# ICS40300-Silicon-Mic_Rev-A_s_y.net
KiCad netlist of a schematic drawn in EAGLE
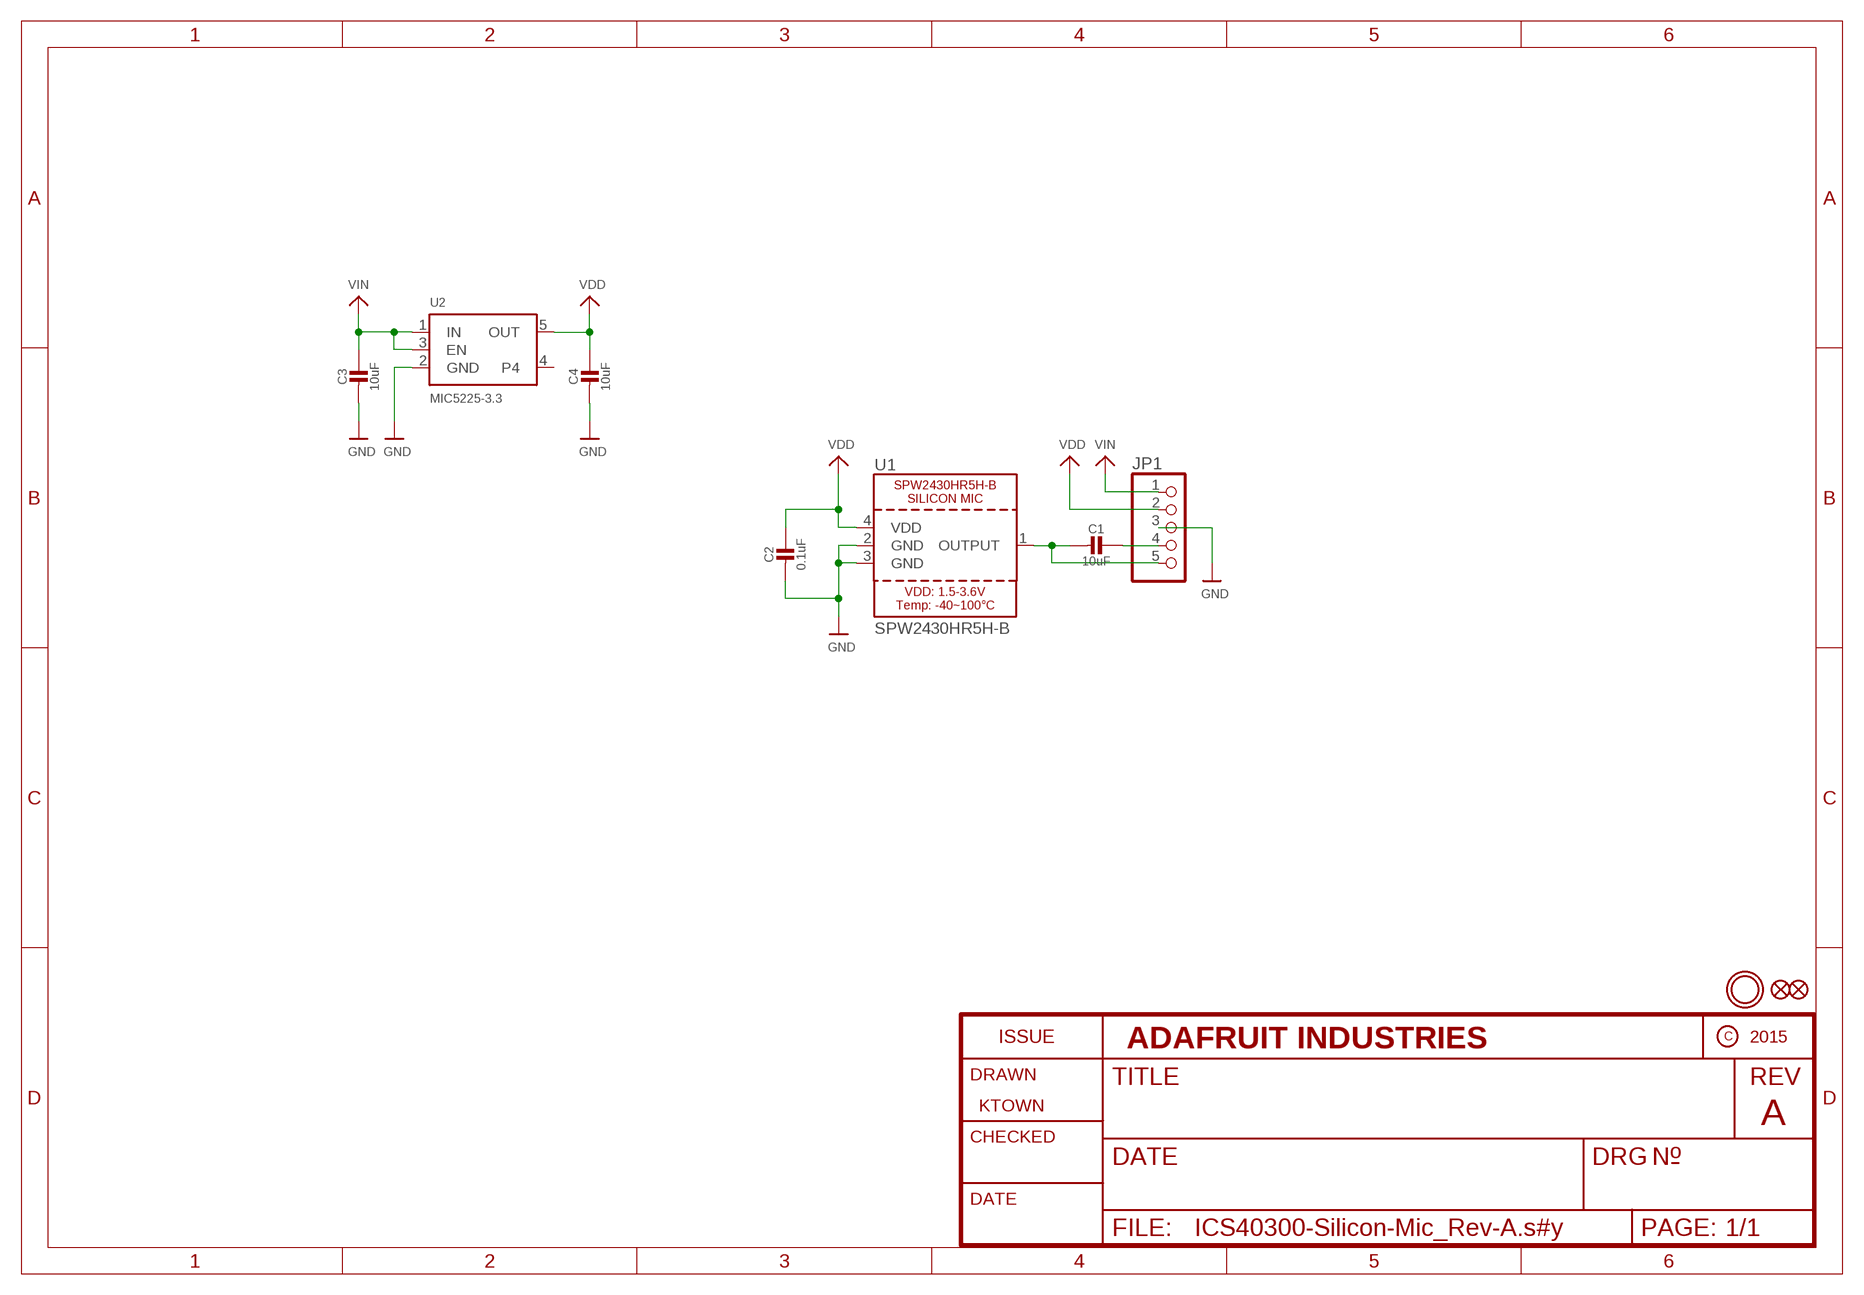
[diagram p0: schematic, sheet 1]

(export (version "E")
  (design (tool "Eeschema 10.0.6"))
  (components
    (comp (ref "C1")
      (value "10uF")
      (footprint "eagle-import:0805-NO")
      (libsource (lib "eagle-import") (part "CAP_CERAMIC0805-NOOUTLINE"))
    )
    (comp (ref "C2")
      (value "0.1uF")
      (footprint "eagle-import:0805-NO")
      (libsource (lib "eagle-import") (part "CAP_CERAMIC0805-NOOUTLINE"))
    )
    (comp (ref "C3")
      (value "10uF")
      (footprint "eagle-import:0805-NO")
      (libsource (lib "eagle-import") (part "CAP_CERAMIC0805-NOOUTLINE"))
    )
    (comp (ref "C4")
      (value "10uF")
      (footprint "eagle-import:0805-NO")
      (libsource (lib "eagle-import") (part "CAP_CERAMIC0805-NOOUTLINE"))
    )
    (comp (ref "FID1")
      (value "FIDUCIAL\"\"")
      (footprint "eagle-import:FIDUCIAL_1MM")
      (libsource (lib "eagle-import") (part "FIDUCIAL{dblquote}{dblquote}"))
    )
    (comp (ref "FID2")
      (value "FIDUCIAL\"\"")
      (footprint "eagle-import:FIDUCIAL_1MM")
      (libsource (lib "eagle-import") (part "FIDUCIAL{dblquote}{dblquote}"))
    )
    (comp (ref "JP1")
      (value "HEADER-1X576MIL")
      (footprint "eagle-import:1X05_ROUND_76")
      (libsource (lib "eagle-import") (part "HEADER-1X576MIL"))
    )
    (comp (ref "U$12")
      (value "MOUNTINGHOLE2.5")
      (footprint "eagle-import:MOUNTINGHOLE_2.5_PLATED")
      (libsource (lib "eagle-import") (part "MOUNTINGHOLE2.5"))
    )
    (comp (ref "U1")
      (value "SPW2430HR5H-B")
      (footprint "eagle-import:SPW2430HR5H-B")
      (libsource (lib "eagle-import") (part "SPW2430HR5H-B"))
    )
    (comp (ref "U2")
      (value "MIC5225-3.3")
      (footprint "eagle-import:SOT23-5")
      (libsource (lib "eagle-import") (part "VREG_SOT23-5"))
    )
  )
  (nets
    (net (code "1") (name "GND") (class "Default")
      (node (ref "C2") (pin "2") (pinfunction "2_2") (pintype "passive"))
      (node (ref "C3") (pin "2") (pinfunction "2_2") (pintype "passive"))
      (node (ref "C4") (pin "2") (pinfunction "2_2") (pintype "passive"))
      (node (ref "JP1") (pin "3") (pinfunction "3_3") (pintype "passive"))
      (node (ref "U1") (pin "2") (pinfunction "GND_2") (pintype "power_in"))
      (node (ref "U1") (pin "3") (pinfunction "GND_3") (pintype "power_in"))
      (node (ref "U2") (pin "2") (pinfunction "GND_2") (pintype "power_in"))
    )
    (net (code "2") (name "Net-(C1-Pad1)") (class "Default")
      (node (ref "C1") (pin "1") (pinfunction "1_1") (pintype "passive"))
      (node (ref "JP1") (pin "4") (pinfunction "4_4") (pintype "passive"))
    )
    (net (code "3") (name "Net-(U1-OUTPUT)") (class "Default")
      (node (ref "C1") (pin "2") (pinfunction "2_2") (pintype "passive"))
      (node (ref "JP1") (pin "5") (pinfunction "5_5") (pintype "passive"))
      (node (ref "U1") (pin "1") (pinfunction "OUTPUT_1") (pintype "output"))
    )
    (net (code "4") (name "VDD") (class "Default")
      (node (ref "C2") (pin "1") (pinfunction "1_1") (pintype "passive"))
      (node (ref "C4") (pin "1") (pinfunction "1_1") (pintype "passive"))
      (node (ref "JP1") (pin "2") (pinfunction "2_2") (pintype "passive"))
      (node (ref "U1") (pin "4") (pinfunction "VDD_4") (pintype "power_in"))
      (node (ref "U2") (pin "5") (pinfunction "OUT_5") (pintype "power_in"))
    )
    (net (code "5") (name "VIN") (class "Default")
      (node (ref "C3") (pin "1") (pinfunction "1_1") (pintype "passive"))
      (node (ref "JP1") (pin "1") (pinfunction "1_1") (pintype "passive"))
      (node (ref "U2") (pin "1") (pinfunction "IN_1") (pintype "power_in"))
      (node (ref "U2") (pin "3") (pinfunction "EN_3") (pintype "input"))
    )
    (net (code "6") (name "unconnected-(U2-P4-Pad4)") (class "Default")
      (node (ref "U2") (pin "4") (pinfunction "P4_4") (pintype "bidirectional"))
    )
  )
)
